# lm317_TCV.net
KiCad netlist of a schematic drawn in EAGLE
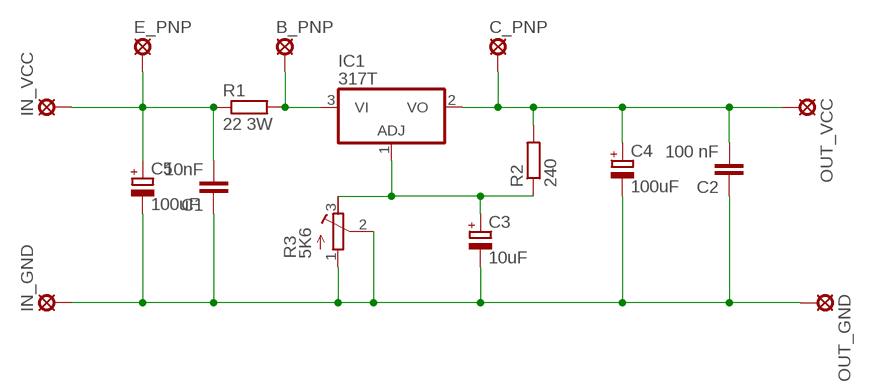
[diagram p0: schematic, sheet 1]

(export (version "E")
  (design (tool "Eeschema 10.0.6"))
  (components
    (comp (ref "B_PNP")
      (value "SE14")
      (footprint "eagle-import:SE14")
      (libsource (lib "eagle-import") (part "SE14"))
    )
    (comp (ref "C1")
      (value "10nF")
      (footprint "eagle-import:C7.5B3")
      (libsource (lib "eagle-import") (part "C7.5/3"))
    )
    (comp (ref "C2")
      (value "100 nF")
      (footprint "eagle-import:C7.5B3")
      (libsource (lib "eagle-import") (part "C7.5/3"))
    )
    (comp (ref "C3")
      (value "10uF")
      (footprint "eagle-import:E2,5-6E")
      (libsource (lib "eagle-import") (part "CPOL-EUE2,5-6E"))
    )
    (comp (ref "C4")
      (value "100uF")
      (footprint "eagle-import:E2,5-6E")
      (libsource (lib "eagle-import") (part "CPOL-EUE2,5-6E"))
    )
    (comp (ref "C5")
      (value "100uF")
      (footprint "eagle-import:E2,5-6E")
      (libsource (lib "eagle-import") (part "CPOL-EUE2,5-6E"))
    )
    (comp (ref "C_PNP")
      (value "SE14")
      (footprint "eagle-import:SE14")
      (libsource (lib "eagle-import") (part "SE14"))
    )
    (comp (ref "E_PNP")
      (value "SE14")
      (footprint "eagle-import:SE14")
      (libsource (lib "eagle-import") (part "SE14"))
    )
    (comp (ref "IC1")
      (value "317T")
      (footprint "eagle-import:TO220H")
      (libsource (lib "eagle-import") (part "317T"))
    )
    (comp (ref "IN_GND")
      (value "SE14")
      (footprint "eagle-import:SE14")
      (libsource (lib "eagle-import") (part "SE14"))
    )
    (comp (ref "IN_VCC")
      (value "SE14")
      (footprint "eagle-import:SE14")
      (libsource (lib "eagle-import") (part "SE14"))
    )
    (comp (ref "OUT_GND")
      (value "SE14")
      (footprint "eagle-import:SE14")
      (libsource (lib "eagle-import") (part "SE14"))
    )
    (comp (ref "OUT_VCC")
      (value "SE14")
      (footprint "eagle-import:SE14")
      (libsource (lib "eagle-import") (part "SE14"))
    )
    (comp (ref "R1")
      (value "22 3W")
      (footprint "eagle-import:0411_12")
      (libsource (lib "eagle-import") (part "R-EU_0411/12"))
    )
    (comp (ref "R2")
      (value "240")
      (footprint "eagle-import:0207_7")
      (libsource (lib "eagle-import") (part "R-EU_0207/7"))
    )
    (comp (ref "R3")
      (value "5K6")
      (footprint "eagle-import:RTRIM3339P")
      (libsource (lib "eagle-import") (part "R-TRIMM3339P"))
    )
  )
  (nets
    (net (code "1") (name "Net-(C1-Pad2)") (class "Default")
      (node (ref "C1") (pin "2") (pinfunction "2_2") (pintype "passive"))
      (node (ref "C5") (pin "+") (pinfunction "+_+") (pintype "passive"))
      (node (ref "E_PNP") (pin "MP") (pinfunction "MP_MP") (pintype "passive"))
      (node (ref "IN_VCC") (pin "MP") (pinfunction "MP_MP") (pintype "passive"))
      (node (ref "R1") (pin "1") (pinfunction "1_1") (pintype "passive"))
    )
    (net (code "2") (name "Net-(IC1-ADJ)") (class "Default")
      (node (ref "C3") (pin "+") (pinfunction "+_+") (pintype "passive"))
      (node (ref "IC1") (pin "1") (pinfunction "ADJ_1") (pintype "input"))
      (node (ref "R2") (pin "1") (pinfunction "1_1") (pintype "passive"))
      (node (ref "R3") (pin "3") (pinfunction "E_3") (pintype "passive"))
    )
    (net (code "3") (name "Net-(IC1-VI)") (class "Default")
      (node (ref "B_PNP") (pin "MP") (pinfunction "MP_MP") (pintype "passive"))
      (node (ref "IC1") (pin "3") (pinfunction "VI_3") (pintype "input"))
      (node (ref "R1") (pin "2") (pinfunction "2_2") (pintype "passive"))
    )
    (net (code "4") (name "Net-(IC1-VO)") (class "Default")
      (node (ref "C2") (pin "2") (pinfunction "2_2") (pintype "passive"))
      (node (ref "C4") (pin "+") (pinfunction "+_+") (pintype "passive"))
      (node (ref "C_PNP") (pin "MP") (pinfunction "MP_MP") (pintype "passive"))
      (node (ref "IC1") (pin "2") (pinfunction "VO_2") (pintype "passive"))
      (node (ref "OUT_VCC") (pin "MP") (pinfunction "MP_MP") (pintype "passive"))
      (node (ref "R2") (pin "2") (pinfunction "2_2") (pintype "passive"))
    )
    (net (code "5") (name "Net-(R3-A)") (class "Default")
      (node (ref "C1") (pin "1") (pinfunction "1_1") (pintype "passive"))
      (node (ref "C2") (pin "1") (pinfunction "1_1") (pintype "passive"))
      (node (ref "C3") (pin "-") (pinfunction "-_-") (pintype "passive"))
      (node (ref "C4") (pin "-") (pinfunction "-_-") (pintype "passive"))
      (node (ref "C5") (pin "-") (pinfunction "-_-") (pintype "passive"))
      (node (ref "IN_GND") (pin "MP") (pinfunction "MP_MP") (pintype "passive"))
      (node (ref "OUT_GND") (pin "MP") (pinfunction "MP_MP") (pintype "passive"))
      (node (ref "R3") (pin "1") (pinfunction "A_1") (pintype "passive"))
      (node (ref "R3") (pin "2") (pinfunction "S_2") (pintype "passive"))
    )
  )
)
